# SH9_-_RS-485.net
KiCad netlist of a schematic drawn in Altium Designer
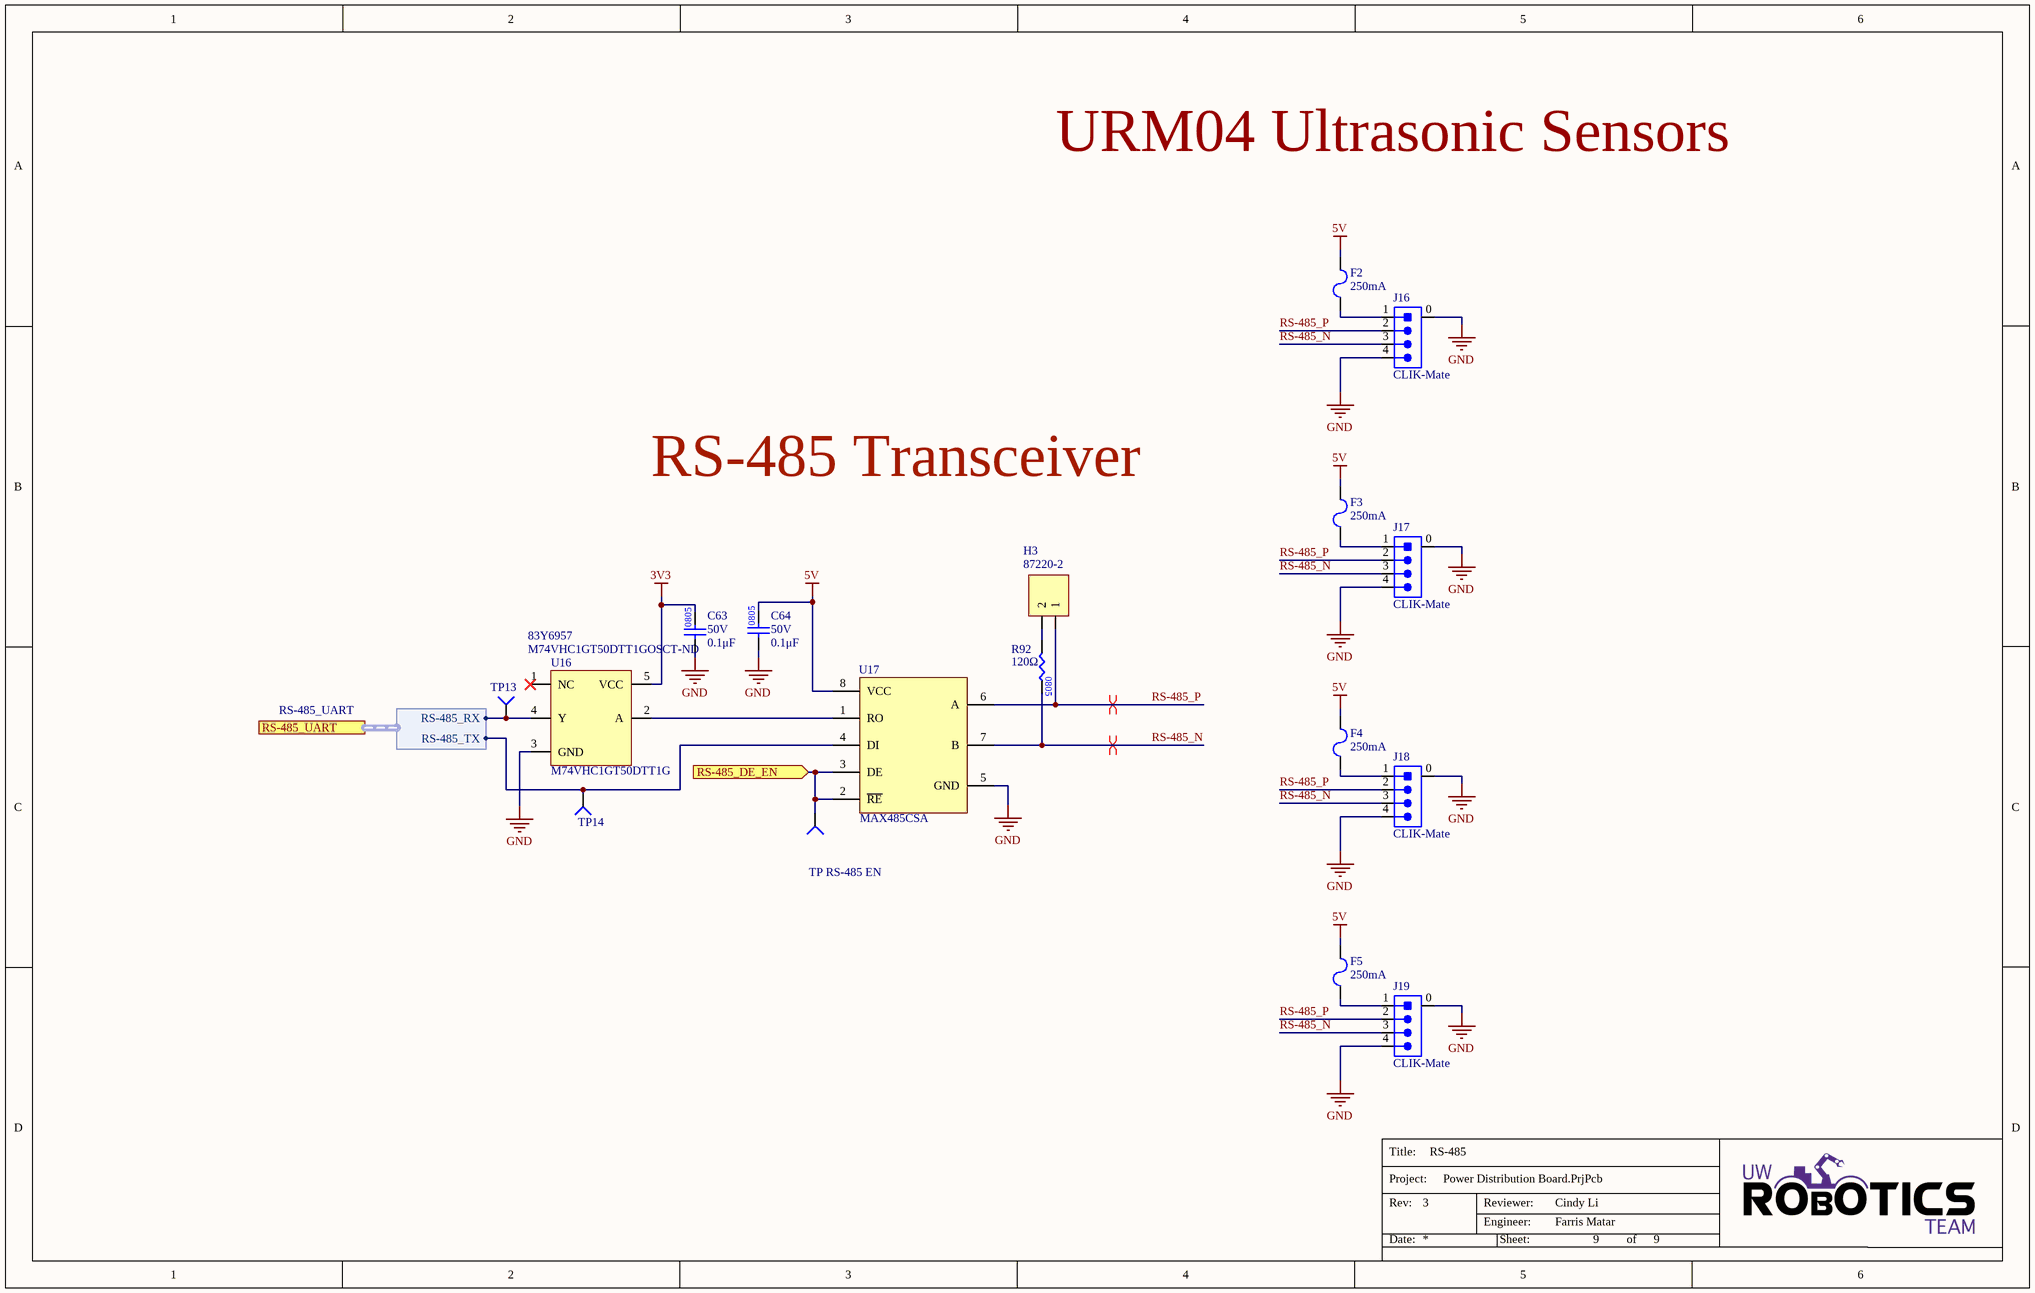
[diagram p0: SH9 - RS-485.SchDoc]

(export (version "E")
  (design (tool "Eeschema 10.0.6"))
  (components
    (comp (ref "C63")
      (value "0.1μF")
      (footprint "CAP2012")
      (description "CAP CER 0.1UF 50V X7R 0805")
      (fields
        (field (name "VOLTAGE RATING") "50V")
        (field (name "LCSC PART #") "C49678")
        (field (name "Comment") "CAP_0.1uF_50V_0805")
      )
      (libsource (lib "UWRT_Schematic_Library_2020") (part "CAP_0.1uF_50V_0805"))
    )
    (comp (ref "C64")
      (value "0.1μF")
      (footprint "CAP2012")
      (description "CAP CER 0.1UF 50V X7R 0805")
      (fields
        (field (name "VOLTAGE RATING") "50V")
        (field (name "LCSC PART #") "C49678")
        (field (name "Comment") "CAP_0.1uF_50V_0805")
      )
      (libsource (lib "UWRT_Schematic_Library_2020") (part "CAP_0.1uF_50V_0805"))
    )
    (comp (ref "F2")
      (value "FUSE_250mA_1206")
      (footprint "FUSE_1206")
      (description "FUSE BOARD MNT 250MA 125VAC/VDC")
      (fields (field (name "CURRENT RATING") "250mA"))
      (libsource (lib "UWRT_Schematic_Library_2020") (part "FUSE_250mA_1206"))
    )
    (comp (ref "F3")
      (value "FUSE_250mA_1206")
      (footprint "FUSE_1206")
      (description "FUSE BOARD MNT 250MA 125VAC/VDC")
      (fields (field (name "CURRENT RATING") "250mA"))
      (libsource (lib "UWRT_Schematic_Library_2020") (part "FUSE_250mA_1206"))
    )
    (comp (ref "F4")
      (value "FUSE_250mA_1206")
      (footprint "FUSE_1206")
      (description "FUSE BOARD MNT 250MA 125VAC/VDC")
      (fields (field (name "CURRENT RATING") "250mA"))
      (libsource (lib "UWRT_Schematic_Library_2020") (part "FUSE_250mA_1206"))
    )
    (comp (ref "F5")
      (value "FUSE_250mA_1206")
      (footprint "FUSE_1206")
      (description "FUSE BOARD MNT 250MA 125VAC/VDC")
      (fields (field (name "CURRENT RATING") "250mA"))
      (libsource (lib "UWRT_Schematic_Library_2020") (part "FUSE_250mA_1206"))
    )
    (comp (ref "H3")
      (value "JUMPER_2")
      (footprint "HDR1X2")
      (description "HEADER 2X1")
      (fields (field (name "MANUFACTURER PART NUMBER 1") "87220-2"))
      (libsource (lib "UWRT_Schematic_Library_2020") (part "JUMPER_2"))
    )
    (comp (ref "J16")
      (value "CON_4M_SM_RA")
      (footprint "MOLEX-5025850470")
      (description "CONN HEADER SMD RIGHT ANGLE 1.5 MM PITCH")
      (fields (field (name "FAMILY") "CLIK-Mate"))
      (libsource (lib "UWRT_Schematic_Library_2020") (part "CON_4M_SM_RA"))
    )
    (comp (ref "J17")
      (value "CON_4M_SM_RA")
      (footprint "MOLEX-5025850470")
      (description "CONN HEADER SMD RIGHT ANGLE 1.5 MM PITCH")
      (fields (field (name "FAMILY") "CLIK-Mate"))
      (libsource (lib "UWRT_Schematic_Library_2020") (part "CON_4M_SM_RA"))
    )
    (comp (ref "J18")
      (value "CON_4M_SM_RA")
      (footprint "MOLEX-5025850470")
      (description "CONN HEADER SMD RIGHT ANGLE 1.5 MM PITCH")
      (fields (field (name "FAMILY") "CLIK-Mate"))
      (libsource (lib "UWRT_Schematic_Library_2020") (part "CON_4M_SM_RA"))
    )
    (comp (ref "J19")
      (value "CON_4M_SM_RA")
      (footprint "MOLEX-5025850470")
      (description "CONN HEADER SMD RIGHT ANGLE 1.5 MM PITCH")
      (fields (field (name "FAMILY") "CLIK-Mate"))
      (libsource (lib "UWRT_Schematic_Library_2020") (part "CON_4M_SM_RA"))
    )
    (comp (ref "R92")
      (value "120Ω")
      (footprint "RES0805")
      (description "RES 120 OHM 1% 1/8W 0805")
      (fields (field (name "LCSC PART #") "C17437") (field (name "Comment") "RES_120Ω_0805_1%"))
      (libsource (lib "UWRT_Schematic_Library_2020") (part "RES_120Ω_0805_1%"))
    )
    (comp (ref "TP RS-485 EN")
      (value "TESTPOINT_1MM_CIRCLE")
      (footprint "TESTPOINT_CIRCLE_1MM")
      (description "TESTPOINT 1MM CIRCLE")
      (libsource (lib "UWRT_Schematic_Library_2020") (part "TESTPOINT_1MM_CIRCLE"))
    )
    (comp (ref "TP13")
      (value "TESTPOINT_1MM_CIRCLE")
      (footprint "TESTPOINT_CIRCLE_1MM")
      (description "TESTPOINT 1MM CIRCLE")
      (libsource (lib "UWRT_Schematic_Library_2020") (part "TESTPOINT_1MM_CIRCLE"))
    )
    (comp (ref "TP14")
      (value "TESTPOINT_1MM_CIRCLE")
      (footprint "TESTPOINT_CIRCLE_1MM")
      (description "TESTPOINT 1MM CIRCLE")
      (libsource (lib "UWRT_Schematic_Library_2020") (part "TESTPOINT_1MM_CIRCLE"))
    )
    (comp (ref "U16")
      (value "IC_BUFFER")
      (footprint "SOT23-5")
      (description "IC BUFFER NON-INVERT 5.5V 5TSOP")
      (fields
        (field (name "MANUFACTURER PART NUMBER 1") "M74VHC1GT50DTT1G")
        (field (name "SUPPLIER PART NUMBER 1") "M74VHC1GT50DTT1GOSCT-ND")
        (field (name "SUPPLIER PART NUMBER 2") "83Y6957")
      )
      (libsource (lib "UWRT_Schematic_Library_2020") (part "IC_BUFFER"))
    )
    (comp (ref "U17")
      (value "MAX485CSA")
      (footprint "SOIC127P600X175-8N")
      (description "IC RS485 TRANSCEIVER HALF 1/1 8SOIC")
      (fields (field (name "LCSC PART #") "C9945"))
      (libsource (lib "UWRT_Schematic_Library_2020") (part "MAX485CSA"))
    )
  )
  (nets
    (net (code "2") (name "/RS-485_DE_EN") (class "Default")
      (node (ref "TP RS-485 EN") (pin "1") (pinfunction "=value_1") (pintype "passive"))
      (node (ref "U17") (pin "2") (pinfunction "~{RE}_2") (pintype "passive"))
      (node (ref "U17") (pin "3") (pinfunction "DE_3") (pintype "passive"))
    )
    (net (code "3") (name "/RS-485_N") (class "Default")
      (node (ref "J16") (pin "3") (pinfunction "3_3") (pintype "passive"))
      (node (ref "J17") (pin "3") (pinfunction "3_3") (pintype "passive"))
      (node (ref "J18") (pin "3") (pinfunction "3_3") (pintype "passive"))
      (node (ref "J19") (pin "3") (pinfunction "3_3") (pintype "passive"))
      (node (ref "R92") (pin "2") (pinfunction "2_2") (pintype "passive"))
      (node (ref "U17") (pin "7") (pinfunction "B_7") (pintype "passive"))
    )
    (net (code "4") (name "/RS-485_P") (class "Default")
      (node (ref "H3") (pin "1") (pinfunction "1_1") (pintype "passive"))
      (node (ref "J16") (pin "2") (pinfunction "2_2") (pintype "passive"))
      (node (ref "J17") (pin "2") (pinfunction "2_2") (pintype "passive"))
      (node (ref "J18") (pin "2") (pinfunction "2_2") (pintype "passive"))
      (node (ref "J19") (pin "2") (pinfunction "2_2") (pintype "passive"))
      (node (ref "U17") (pin "6") (pinfunction "A_6") (pintype "passive"))
    )
    (net (code "6") (name "3V3") (class "Default")
      (node (ref "C63") (pin "2") (pinfunction "2_2") (pintype "passive"))
      (node (ref "U16") (pin "5") (pinfunction "VCC_5") (pintype "passive"))
    )
    (net (code "7") (name "5V") (class "Default")
      (node (ref "C64") (pin "2") (pinfunction "2_2") (pintype "passive"))
      (node (ref "F2") (pin "2") (pinfunction "2_2") (pintype "passive"))
      (node (ref "F3") (pin "2") (pinfunction "2_2") (pintype "passive"))
      (node (ref "F4") (pin "2") (pinfunction "2_2") (pintype "passive"))
      (node (ref "F5") (pin "2") (pinfunction "2_2") (pintype "passive"))
      (node (ref "U17") (pin "8") (pinfunction "VCC_8") (pintype "power_in"))
    )
    (net (code "8") (name "GND") (class "Default")
      (node (ref "C63") (pin "1") (pinfunction "1_1") (pintype "passive"))
      (node (ref "C64") (pin "1") (pinfunction "1_1") (pintype "passive"))
      (node (ref "J16") (pin "0") (pinfunction "0_0") (pintype "passive"))
      (node (ref "J16") (pin "4") (pinfunction "4_4") (pintype "passive"))
      (node (ref "J17") (pin "0") (pinfunction "0_0") (pintype "passive"))
      (node (ref "J17") (pin "4") (pinfunction "4_4") (pintype "passive"))
      (node (ref "J18") (pin "0") (pinfunction "0_0") (pintype "passive"))
      (node (ref "J18") (pin "4") (pinfunction "4_4") (pintype "passive"))
      (node (ref "J19") (pin "0") (pinfunction "0_0") (pintype "passive"))
      (node (ref "J19") (pin "4") (pinfunction "4_4") (pintype "passive"))
      (node (ref "U16") (pin "3") (pinfunction "GND_3") (pintype "passive"))
      (node (ref "U17") (pin "5") (pinfunction "GND_5") (pintype "power_in"))
    )
    (net (code "9") (name "Net-(F2-Pad1)") (class "Default")
      (node (ref "F2") (pin "1") (pinfunction "1_1") (pintype "passive"))
      (node (ref "J16") (pin "1") (pinfunction "1_1") (pintype "passive"))
    )
    (net (code "10") (name "Net-(F3-Pad1)") (class "Default")
      (node (ref "F3") (pin "1") (pinfunction "1_1") (pintype "passive"))
      (node (ref "J17") (pin "1") (pinfunction "1_1") (pintype "passive"))
    )
    (net (code "11") (name "Net-(F4-Pad1)") (class "Default")
      (node (ref "F4") (pin "1") (pinfunction "1_1") (pintype "passive"))
      (node (ref "J18") (pin "1") (pinfunction "1_1") (pintype "passive"))
    )
    (net (code "12") (name "Net-(F5-Pad1)") (class "Default")
      (node (ref "F5") (pin "1") (pinfunction "1_1") (pintype "passive"))
      (node (ref "J19") (pin "1") (pinfunction "1_1") (pintype "passive"))
    )
    (net (code "13") (name "Net-(H3-Pad2)") (class "Default")
      (node (ref "H3") (pin "2") (pinfunction "2_2") (pintype "passive"))
      (node (ref "R92") (pin "1") (pinfunction "1_1") (pintype "passive"))
    )
    (net (code "14") (name "Net-(TP13-=value)") (class "Default")
      (node (ref "TP13") (pin "1") (pinfunction "=value_1") (pintype "passive"))
      (node (ref "U16") (pin "4") (pinfunction "Y_4") (pintype "passive"))
    )
    (net (code "15") (name "Net-(TP14-=value)") (class "Default")
      (node (ref "TP14") (pin "1") (pinfunction "=value_1") (pintype "passive"))
      (node (ref "U17") (pin "4") (pinfunction "DI_4") (pintype "passive"))
    )
    (net (code "16") (name "Net-(U16-A)") (class "Default")
      (node (ref "U16") (pin "2") (pinfunction "A_2") (pintype "passive"))
      (node (ref "U17") (pin "1") (pinfunction "RO_1") (pintype "passive"))
    )
    (net (code "17") (name "unconnected-(U16-NC-Pad1)") (class "Default")
      (node (ref "U16") (pin "1") (pinfunction "NC_1") (pintype "passive+no_connect"))
    )
  )
)
